# brushless_sub_driver_4.net
KiCad netlist of a schematic drawn in EAGLE
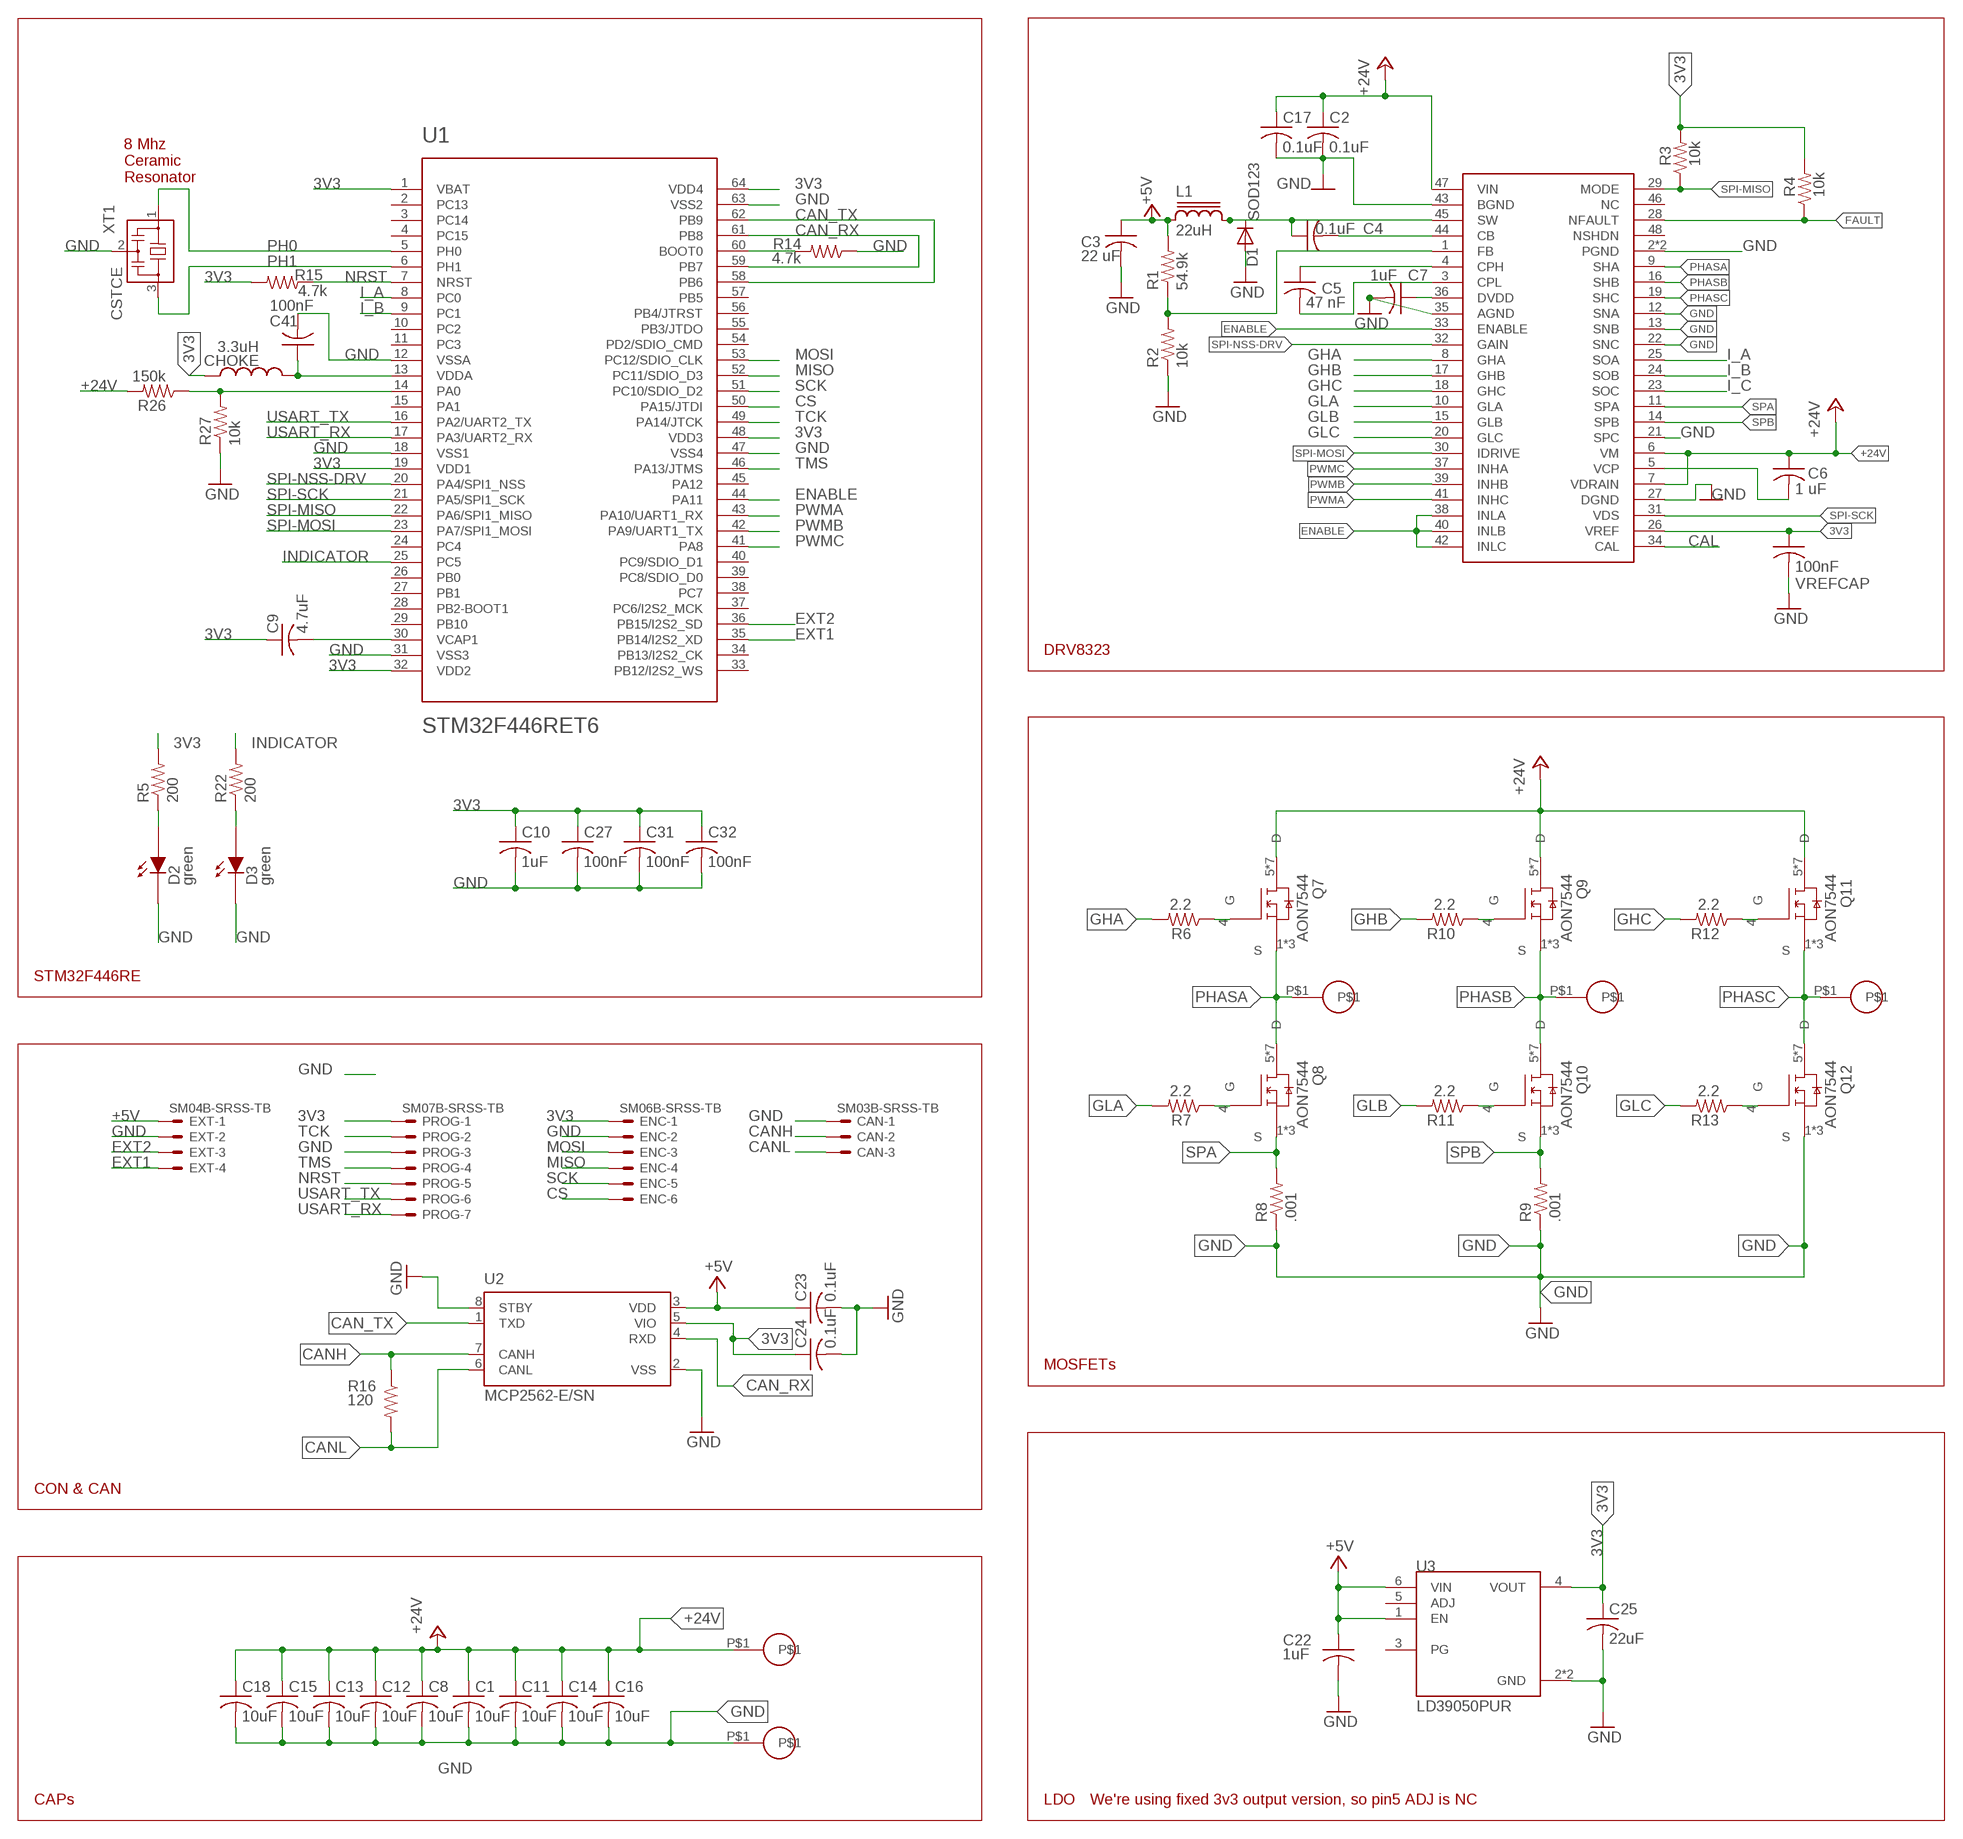
[diagram p0: schematic, sheet 1]

(export (version "E")
  (design (tool "Eeschema 10.0.6"))
  (components
    (comp (ref "C1")
      (value "10uF")
      (footprint "eagle-import:C1206K")
      (libsource (lib "eagle-import") (part "C-USC1206K"))
    )
    (comp (ref "C2")
      (value "0.1uF")
      (footprint "eagle-import:C0603K")
      (libsource (lib "eagle-import") (part "C-USC0603K"))
    )
    (comp (ref "C3")
      (value "22 uF")
      (footprint "eagle-import:C0603K")
      (libsource (lib "eagle-import") (part "C-USC0603K"))
    )
    (comp (ref "C4")
      (value "0.1uF")
      (footprint "eagle-import:C0603K")
      (libsource (lib "eagle-import") (part "C-USC0603K"))
    )
    (comp (ref "C5")
      (value "47 nF")
      (footprint "eagle-import:C0402K")
      (libsource (lib "eagle-import") (part "C-USC0402K"))
    )
    (comp (ref "C6")
      (value "1 uF")
      (footprint "eagle-import:C0603K")
      (libsource (lib "eagle-import") (part "C-USC0603K"))
    )
    (comp (ref "C7")
      (value "1uF")
      (footprint "eagle-import:C0402K")
      (libsource (lib "eagle-import") (part "C-USC0402K"))
    )
    (comp (ref "C8")
      (value "10uF")
      (footprint "eagle-import:C1206K")
      (libsource (lib "eagle-import") (part "C-USC1206K"))
    )
    (comp (ref "C9")
      (value "4.7uF")
      (footprint "eagle-import:C0402K")
      (libsource (lib "eagle-import") (part "C-USC0402K"))
    )
    (comp (ref "C10")
      (value "1uF")
      (footprint "eagle-import:C0402K")
      (libsource (lib "eagle-import") (part "C-USC0402K"))
    )
    (comp (ref "C11")
      (value "10uF")
      (footprint "eagle-import:C1206K")
      (libsource (lib "eagle-import") (part "C-USC1206K"))
    )
    (comp (ref "C12")
      (value "10uF")
      (footprint "eagle-import:C1206K")
      (libsource (lib "eagle-import") (part "C-USC1206K"))
    )
    (comp (ref "C13")
      (value "10uF")
      (footprint "eagle-import:C1206K")
      (libsource (lib "eagle-import") (part "C-USC1206K"))
    )
    (comp (ref "C14")
      (value "10uF")
      (footprint "eagle-import:C1206K")
      (libsource (lib "eagle-import") (part "C-USC1206K"))
    )
    (comp (ref "C15")
      (value "10uF")
      (footprint "eagle-import:C1206K")
      (libsource (lib "eagle-import") (part "C-USC1206K"))
    )
    (comp (ref "C16")
      (value "10uF")
      (footprint "eagle-import:C1206K")
      (libsource (lib "eagle-import") (part "C-USC1206K"))
    )
    (comp (ref "C17")
      (value "0.1uF")
      (footprint "eagle-import:C1206K")
      (libsource (lib "eagle-import") (part "C-USC1206K"))
    )
    (comp (ref "C18")
      (value "10uF")
      (footprint "eagle-import:C1206K")
      (libsource (lib "eagle-import") (part "C-USC1206K"))
    )
    (comp (ref "C22")
      (value "1uF")
      (footprint "eagle-import:C0402")
      (libsource (lib "eagle-import") (part "C-USC0402"))
    )
    (comp (ref "C23")
      (value "0.1uF")
      (footprint "eagle-import:C0603K")
      (libsource (lib "eagle-import") (part "C-USC0603K"))
    )
    (comp (ref "C24")
      (value "0.1uF")
      (footprint "eagle-import:C0603K")
      (libsource (lib "eagle-import") (part "C-USC0603K"))
    )
    (comp (ref "C25")
      (value "22uF")
      (footprint "eagle-import:C0603K")
      (libsource (lib "eagle-import") (part "C-USC0603K"))
    )
    (comp (ref "C27")
      (value "100nF")
      (footprint "eagle-import:C0402K")
      (libsource (lib "eagle-import") (part "C-USC0402K"))
    )
    (comp (ref "C31")
      (value "100nF")
      (footprint "eagle-import:C0402K")
      (libsource (lib "eagle-import") (part "C-USC0402K"))
    )
    (comp (ref "C32")
      (value "100nF")
      (footprint "eagle-import:C0402K")
      (libsource (lib "eagle-import") (part "C-USC0402K"))
    )
    (comp (ref "C41")
      (value "100nF")
      (footprint "eagle-import:C0402")
      (libsource (lib "eagle-import") (part "C-USC0402"))
    )
    (comp (ref "CAN")
      (value "SM03B-SRSS-TB")
      (footprint "eagle-import:SM03B-SRSS-TB")
      (libsource (lib "eagle-import") (part "?M03B-SRSS-TBS"))
    )
    (comp (ref "CHOKE")
      (value "3.3uH")
      (footprint "eagle-import:0603")
      (libsource (lib "eagle-import") (part "INDUCTOR0603"))
    )
    (comp (ref "D1")
      (value "SOD123")
      (footprint "eagle-import:SOD123")
      (libsource (lib "eagle-import") (part "DIODE-SOD123"))
    )
    (comp (ref "D2")
      (value "green")
      (footprint "eagle-import:0603P")
      (libsource (lib "eagle-import") (part "LEDB"))
    )
    (comp (ref "D3")
      (value "green")
      (footprint "eagle-import:0603P")
      (libsource (lib "eagle-import") (part "LEDB"))
    )
    (comp (ref "DRV1")
      (value "DRV8323RH")
      (footprint "eagle-import:QFN50P700X700X90-49N")
      (libsource (lib "eagle-import") (part "DRV8323RH"))
    )
    (comp (ref "ENC")
      (value "SM06B-SRSS-TB")
      (footprint "eagle-import:SM06B-SRSS-TB")
      (libsource (lib "eagle-import") (part "?M06B-SRSS-TBS"))
    )
    (comp (ref "EXT")
      (value "SM04B-SRSS-TB")
      (footprint "eagle-import:SM04B-SRSS-TB")
      (libsource (lib "eagle-import") (part "?M04B-SRSS-TBS"))
    )
    (comp (ref "L1")
      (value "22uH")
      (footprint "eagle-import:SDR0302")
      (libsource (lib "eagle-import") (part "SDR0302"))
    )
    (comp (ref "O_A")
      (value "18_AWG_PAD")
      (footprint "eagle-import:18_AWG_PAD")
      (libsource (lib "eagle-import") (part "18_AWG_PAD"))
    )
    (comp (ref "O_B")
      (value "18_AWG_PAD")
      (footprint "eagle-import:18_AWG_PAD")
      (libsource (lib "eagle-import") (part "18_AWG_PAD"))
    )
    (comp (ref "O_C")
      (value "18_AWG_PAD")
      (footprint "eagle-import:18_AWG_PAD")
      (libsource (lib "eagle-import") (part "18_AWG_PAD"))
    )
    (comp (ref "PROG")
      (value "SM07B-SRSS-TB")
      (footprint "eagle-import:SM07B-SRSS-TB")
      (libsource (lib "eagle-import") (part "?M07B-SRSS-TBS"))
    )
    (comp (ref "Q7")
      (value "AON7544")
      (footprint "eagle-import:AON7544")
      (libsource (lib "eagle-import") (part "AON7544"))
    )
    (comp (ref "Q8")
      (value "AON7544")
      (footprint "eagle-import:AON7544")
      (libsource (lib "eagle-import") (part "AON7544"))
    )
    (comp (ref "Q9")
      (value "AON7544")
      (footprint "eagle-import:AON7544")
      (libsource (lib "eagle-import") (part "AON7544"))
    )
    (comp (ref "Q10")
      (value "AON7544")
      (footprint "eagle-import:AON7544")
      (libsource (lib "eagle-import") (part "AON7544"))
    )
    (comp (ref "Q11")
      (value "AON7544")
      (footprint "eagle-import:AON7544")
      (libsource (lib "eagle-import") (part "AON7544"))
    )
    (comp (ref "Q12")
      (value "AON7544")
      (footprint "eagle-import:AON7544")
      (libsource (lib "eagle-import") (part "AON7544"))
    )
    (comp (ref "R1")
      (value "54.9k")
      (footprint "eagle-import:R0402")
      (libsource (lib "eagle-import") (part "R-US_R0402"))
    )
    (comp (ref "R2")
      (value "10k")
      (footprint "eagle-import:R0402")
      (libsource (lib "eagle-import") (part "R-US_R0402"))
    )
    (comp (ref "R3")
      (value "10k")
      (footprint "eagle-import:R0402")
      (libsource (lib "eagle-import") (part "R-US_R0402"))
    )
    (comp (ref "R4")
      (value "10k")
      (footprint "eagle-import:R0402")
      (libsource (lib "eagle-import") (part "R-US_R0402"))
    )
    (comp (ref "R5")
      (value "200")
      (footprint "eagle-import:R0402")
      (libsource (lib "eagle-import") (part "R-US_R0402"))
    )
    (comp (ref "R6")
      (value "2.2")
      (footprint "eagle-import:R0402")
      (libsource (lib "eagle-import") (part "R-US_R0402"))
    )
    (comp (ref "R7")
      (value "2.2")
      (footprint "eagle-import:R0402")
      (libsource (lib "eagle-import") (part "R-US_R0402"))
    )
    (comp (ref "R8")
      (value ".001")
      (footprint "eagle-import:R1210")
      (libsource (lib "eagle-import") (part "R-US_R1210"))
    )
    (comp (ref "R9")
      (value ".001")
      (footprint "eagle-import:R1210")
      (libsource (lib "eagle-import") (part "R-US_R1210"))
    )
    (comp (ref "R10")
      (value "2.2")
      (footprint "eagle-import:R0402")
      (libsource (lib "eagle-import") (part "R-US_R0402"))
    )
    (comp (ref "R11")
      (value "2.2")
      (footprint "eagle-import:R0402")
      (libsource (lib "eagle-import") (part "R-US_R0402"))
    )
    (comp (ref "R12")
      (value "2.2")
      (footprint "eagle-import:R0402")
      (libsource (lib "eagle-import") (part "R-US_R0402"))
    )
    (comp (ref "R13")
      (value "2.2")
      (footprint "eagle-import:R0402")
      (libsource (lib "eagle-import") (part "R-US_R0402"))
    )
    (comp (ref "R14")
      (value "4.7k")
      (footprint "eagle-import:R0402")
      (libsource (lib "eagle-import") (part "R-US_R0402"))
    )
    (comp (ref "R15")
      (value "4.7k")
      (footprint "eagle-import:R0402")
      (libsource (lib "eagle-import") (part "R-US_R0402"))
    )
    (comp (ref "R16")
      (value "120")
      (footprint "eagle-import:R0603")
      (libsource (lib "eagle-import") (part "R-US_R0603"))
    )
    (comp (ref "R22")
      (value "200")
      (footprint "eagle-import:R0402")
      (libsource (lib "eagle-import") (part "R-US_R0402"))
    )
    (comp (ref "R26")
      (value "150k")
      (footprint "eagle-import:R0402")
      (libsource (lib "eagle-import") (part "R-US_R0402"))
    )
    (comp (ref "R27")
      (value "10k")
      (footprint "eagle-import:R0402")
      (libsource (lib "eagle-import") (part "R-US_R0402"))
    )
    (comp (ref "U$8")
      (value "18_AWG_PAD")
      (footprint "eagle-import:18_AWG_PAD")
      (libsource (lib "eagle-import") (part "18_AWG_PAD"))
    )
    (comp (ref "U$10")
      (value "18_AWG_PAD")
      (footprint "eagle-import:18_AWG_PAD")
      (libsource (lib "eagle-import") (part "18_AWG_PAD"))
    )
    (comp (ref "U1")
      (value "STM32F446RET6")
      (footprint "eagle-import:TQFP64")
      (libsource (lib "eagle-import") (part "STM32F446RET6"))
    )
    (comp (ref "U2")
      (value "MCP2562-E/SN")
      (footprint "eagle-import:SOIC127P600X175-8N")
      (fields (field (name "MF") "Microchip"))
      (libsource (lib "eagle-import") (part "MCP2562-E/SN"))
    )
    (comp (ref "U3")
      (value "LD39050PUR")
      (footprint "eagle-import:SON95P300X300X100-7N")
      (fields (field (name "MF") "STMicroelectronics"))
      (libsource (lib "eagle-import") (part "LD39050PUR"))
    )
    (comp (ref "VREFCAP")
      (value "100nF")
      (footprint "eagle-import:C0402K")
      (libsource (lib "eagle-import") (part "C-USC0402K"))
    )
    (comp (ref "XT1")
      (value "CSTCE")
      (footprint "eagle-import:CSTCE")
      (libsource (lib "eagle-import") (part "CSTCE"))
    )
  )
  (nets
    (net (code "1") (name "+5V") (class "Default")
      (node (ref "C22") (pin "1") (pinfunction "1_1") (pintype "passive"))
      (node (ref "C23") (pin "1") (pinfunction "1_1") (pintype "passive"))
      (node (ref "C3") (pin "1") (pinfunction "1_1") (pintype "passive"))
      (node (ref "EXT") (pin "1") (pinfunction "S_1") (pintype "passive"))
      (node (ref "L1") (pin "1") (pinfunction "1_1") (pintype "passive"))
      (node (ref "R1") (pin "2") (pinfunction "2_2") (pintype "passive"))
      (node (ref "U2") (pin "3") (pinfunction "VDD_3") (pintype "power_in"))
      (node (ref "U3") (pin "1") (pinfunction "EN_1") (pintype "input"))
      (node (ref "U3") (pin "6") (pinfunction "VIN_6") (pintype "input"))
    )
    (net (code "2") (name "+24V") (class "Default")
      (node (ref "C1") (pin "1") (pinfunction "1_1") (pintype "passive"))
      (node (ref "C11") (pin "1") (pinfunction "1_1") (pintype "passive"))
      (node (ref "C12") (pin "1") (pinfunction "1_1") (pintype "passive"))
      (node (ref "C13") (pin "1") (pinfunction "1_1") (pintype "passive"))
      (node (ref "C14") (pin "1") (pinfunction "1_1") (pintype "passive"))
      (node (ref "C15") (pin "1") (pinfunction "1_1") (pintype "passive"))
      (node (ref "C16") (pin "1") (pinfunction "1_1") (pintype "passive"))
      (node (ref "C17") (pin "1") (pinfunction "1_1") (pintype "passive"))
      (node (ref "C18") (pin "1") (pinfunction "1_1") (pintype "passive"))
      (node (ref "C2") (pin "1") (pinfunction "1_1") (pintype "passive"))
      (node (ref "C6") (pin "1") (pinfunction "1_1") (pintype "passive"))
      (node (ref "C8") (pin "1") (pinfunction "1_1") (pintype "passive"))
      (node (ref "DRV1") (pin "47") (pinfunction "VIN_47") (pintype "bidirectional"))
      (node (ref "DRV1") (pin "6") (pinfunction "VM_6") (pintype "bidirectional"))
      (node (ref "DRV1") (pin "7") (pinfunction "VDRAIN_7") (pintype "bidirectional"))
      (node (ref "Q11") (pin "10") (pinfunction "D_10") (pintype "bidirectional"))
      (node (ref "Q11") (pin "11") (pinfunction "D_11") (pintype "bidirectional"))
      (node (ref "Q11") (pin "5") (pinfunction "D_5") (pintype "bidirectional"))
      (node (ref "Q11") (pin "6") (pinfunction "D_6") (pintype "bidirectional"))
      (node (ref "Q11") (pin "7") (pinfunction "D_7") (pintype "bidirectional"))
      (node (ref "Q11") (pin "8") (pinfunction "D_8") (pintype "bidirectional"))
      (node (ref "Q11") (pin "9") (pinfunction "D_9") (pintype "bidirectional"))
      (node (ref "Q7") (pin "10") (pinfunction "D_10") (pintype "bidirectional"))
      (node (ref "Q7") (pin "11") (pinfunction "D_11") (pintype "bidirectional"))
      (node (ref "Q7") (pin "5") (pinfunction "D_5") (pintype "bidirectional"))
      (node (ref "Q7") (pin "6") (pinfunction "D_6") (pintype "bidirectional"))
      (node (ref "Q7") (pin "7") (pinfunction "D_7") (pintype "bidirectional"))
      (node (ref "Q7") (pin "8") (pinfunction "D_8") (pintype "bidirectional"))
      (node (ref "Q7") (pin "9") (pinfunction "D_9") (pintype "bidirectional"))
      (node (ref "Q9") (pin "10") (pinfunction "D_10") (pintype "bidirectional"))
      (node (ref "Q9") (pin "11") (pinfunction "D_11") (pintype "bidirectional"))
      (node (ref "Q9") (pin "5") (pinfunction "D_5") (pintype "bidirectional"))
      (node (ref "Q9") (pin "6") (pinfunction "D_6") (pintype "bidirectional"))
      (node (ref "Q9") (pin "7") (pinfunction "D_7") (pintype "bidirectional"))
      (node (ref "Q9") (pin "8") (pinfunction "D_8") (pintype "bidirectional"))
      (node (ref "Q9") (pin "9") (pinfunction "D_9") (pintype "bidirectional"))
      (node (ref "R26") (pin "2") (pinfunction "2_2") (pintype "passive"))
      (node (ref "U$8") (pin "P$1") (pinfunction "P$1_P$1") (pintype "bidirectional"))
    )
    (net (code "3") (name "/CAL") (class "Default")
      (node (ref "DRV1") (pin "34") (pinfunction "CAL_34") (pintype "bidirectional"))
    )
    (net (code "4") (name "/CS") (class "Default")
      (node (ref "ENC") (pin "6") (pinfunction "S_6") (pintype "passive"))
      (node (ref "U1") (pin "50") (pinfunction "PA15/JTDI_50") (pintype "bidirectional"))
    )
    (net (code "5") (name "/EXT1") (class "Default")
      (node (ref "EXT") (pin "4") (pinfunction "S_4") (pintype "passive"))
      (node (ref "U1") (pin "35") (pinfunction "PB14/I2S2_XD_35") (pintype "bidirectional"))
    )
    (net (code "6") (name "/EXT2") (class "Default")
      (node (ref "EXT") (pin "3") (pinfunction "S_3") (pintype "passive"))
      (node (ref "U1") (pin "36") (pinfunction "PB15/I2S2_SD_36") (pintype "bidirectional"))
    )
    (net (code "7") (name "/INDICATOR") (class "Default")
      (node (ref "R22") (pin "2") (pinfunction "2_2") (pintype "passive"))
      (node (ref "U1") (pin "25") (pinfunction "PC5_25") (pintype "bidirectional"))
    )
    (net (code "8") (name "/I_A") (class "Default")
      (node (ref "DRV1") (pin "25") (pinfunction "SOA_25") (pintype "bidirectional"))
      (node (ref "U1") (pin "8") (pinfunction "PC0_8") (pintype "bidirectional"))
    )
    (net (code "9") (name "/I_B") (class "Default")
      (node (ref "DRV1") (pin "24") (pinfunction "SOB_24") (pintype "bidirectional"))
      (node (ref "U1") (pin "9") (pinfunction "PC1_9") (pintype "bidirectional"))
    )
    (net (code "10") (name "/I_C") (class "Default")
      (node (ref "DRV1") (pin "23") (pinfunction "SOC_23") (pintype "bidirectional"))
    )
    (net (code "11") (name "/MISO") (class "Default")
      (node (ref "ENC") (pin "4") (pinfunction "S_4") (pintype "passive"))
      (node (ref "U1") (pin "52") (pinfunction "PC11/SDIO_D3_52") (pintype "bidirectional"))
    )
    (net (code "12") (name "/MOSI") (class "Default")
      (node (ref "ENC") (pin "3") (pinfunction "S_3") (pintype "passive"))
      (node (ref "U1") (pin "53") (pinfunction "PC12/SDIO_CLK_53") (pintype "bidirectional"))
    )
    (net (code "13") (name "/NRST") (class "Default")
      (node (ref "PROG") (pin "5") (pinfunction "S_5") (pintype "passive"))
      (node (ref "R15") (pin "1") (pinfunction "1_1") (pintype "passive"))
      (node (ref "U1") (pin "7") (pinfunction "NRST_7") (pintype "bidirectional"))
    )
    (net (code "14") (name "/PH0") (class "Default")
      (node (ref "U1") (pin "5") (pinfunction "PH0_5") (pintype "bidirectional"))
      (node (ref "XT1") (pin "1") (pinfunction "1_1") (pintype "passive"))
    )
    (net (code "15") (name "/PH1") (class "Default")
      (node (ref "U1") (pin "6") (pinfunction "PH1_6") (pintype "bidirectional"))
      (node (ref "XT1") (pin "3") (pinfunction "3_3") (pintype "passive"))
    )
    (net (code "16") (name "/SCK") (class "Default")
      (node (ref "ENC") (pin "5") (pinfunction "S_5") (pintype "passive"))
      (node (ref "U1") (pin "51") (pinfunction "PC10/SDIO_D2_51") (pintype "bidirectional"))
    )
    (net (code "17") (name "/TCK") (class "Default")
      (node (ref "PROG") (pin "2") (pinfunction "S_2") (pintype "passive"))
      (node (ref "U1") (pin "49") (pinfunction "PA14/JTCK_49") (pintype "bidirectional"))
    )
    (net (code "18") (name "/TMS") (class "Default")
      (node (ref "PROG") (pin "4") (pinfunction "S_4") (pintype "passive"))
      (node (ref "U1") (pin "46") (pinfunction "PA13/JTMS_46") (pintype "bidirectional"))
    )
    (net (code "19") (name "/USART_RX") (class "Default")
      (node (ref "PROG") (pin "7") (pinfunction "S_7") (pintype "passive"))
      (node (ref "U1") (pin "17") (pinfunction "PA3/UART2_RX_17") (pintype "bidirectional"))
    )
    (net (code "20") (name "/USART_TX") (class "Default")
      (node (ref "PROG") (pin "6") (pinfunction "S_6") (pintype "passive"))
      (node (ref "U1") (pin "16") (pinfunction "PA2/UART2_TX_16") (pintype "bidirectional"))
    )
    (net (code "21") (name "3V3") (class "Default")
      (node (ref "C10") (pin "1") (pinfunction "1_1") (pintype "passive"))
      (node (ref "C24") (pin "1") (pinfunction "1_1") (pintype "passive"))
      (node (ref "C25") (pin "1") (pinfunction "1_1") (pintype "passive"))
      (node (ref "C27") (pin "1") (pinfunction "1_1") (pintype "passive"))
      (node (ref "C31") (pin "1") (pinfunction "1_1") (pintype "passive"))
      (node (ref "C32") (pin "1") (pinfunction "1_1") (pintype "passive"))
      (node (ref "C9") (pin "1") (pinfunction "1_1") (pintype "passive"))
      (node (ref "CHOKE") (pin "1") (pinfunction "1_1") (pintype "passive"))
      (node (ref "DRV1") (pin "26") (pinfunction "VREF_26") (pintype "bidirectional"))
      (node (ref "ENC") (pin "1") (pinfunction "S_1") (pintype "passive"))
      (node (ref "PROG") (pin "1") (pinfunction "S_1") (pintype "passive"))
      (node (ref "R15") (pin "2") (pinfunction "2_2") (pintype "passive"))
      (node (ref "R3") (pin "2") (pinfunction "2_2") (pintype "passive"))
      (node (ref "R4") (pin "2") (pinfunction "2_2") (pintype "passive"))
      (node (ref "R5") (pin "2") (pinfunction "2_2") (pintype "passive"))
      (node (ref "U1") (pin "1") (pinfunction "VBAT_1") (pintype "bidirectional"))
      (node (ref "U1") (pin "19") (pinfunction "VDD1_19") (pintype "bidirectional"))
      (node (ref "U1") (pin "32") (pinfunction "VDD2_32") (pintype "bidirectional"))
      (node (ref "U1") (pin "48") (pinfunction "VDD3_48") (pintype "bidirectional"))
      (node (ref "U1") (pin "64") (pinfunction "VDD4_64") (pintype "bidirectional"))
      (node (ref "U2") (pin "5") (pinfunction "VIO_5") (pintype "power_in"))
      (node (ref "U3") (pin "4") (pinfunction "VOUT_4") (pintype "output"))
      (node (ref "VREFCAP") (pin "1") (pinfunction "1_1") (pintype "passive"))
    )
    (net (code "22") (name "CANH") (class "Default")
      (node (ref "CAN") (pin "2") (pinfunction "S_2") (pintype "passive"))
      (node (ref "R16") (pin "1") (pinfunction "1_1") (pintype "passive"))
      (node (ref "U2") (pin "7") (pinfunction "CANH_7") (pintype "input"))
    )
    (net (code "23") (name "CANL") (class "Default")
      (node (ref "CAN") (pin "3") (pinfunction "S_3") (pintype "passive"))
      (node (ref "R16") (pin "2") (pinfunction "2_2") (pintype "passive"))
      (node (ref "U2") (pin "6") (pinfunction "CANL_6") (pintype "input"))
    )
    (net (code "24") (name "CAN_RX") (class "Default")
      (node (ref "U1") (pin "59") (pinfunction "PB7_59") (pintype "bidirectional"))
      (node (ref "U1") (pin "61") (pinfunction "PB8_61") (pintype "bidirectional"))
      (node (ref "U2") (pin "4") (pinfunction "RXD_4") (pintype "output"))
    )
    (net (code "25") (name "CAN_TX") (class "Default")
      (node (ref "U1") (pin "58") (pinfunction "PB6_58") (pintype "bidirectional"))
      (node (ref "U1") (pin "62") (pinfunction "PB9_62") (pintype "bidirectional"))
      (node (ref "U2") (pin "1") (pinfunction "TXD_1") (pintype "input"))
    )
    (net (code "26") (name "ENABLE") (class "Default")
      (node (ref "DRV1") (pin "33") (pinfunction "ENABLE_33") (pintype "bidirectional"))
      (node (ref "DRV1") (pin "38") (pinfunction "INLA_38") (pintype "bidirectional"))
      (node (ref "DRV1") (pin "40") (pinfunction "INLB_40") (pintype "bidirectional"))
      (node (ref "DRV1") (pin "42") (pinfunction "INLC_42") (pintype "bidirectional"))
      (node (ref "U1") (pin "44") (pinfunction "PA11_44") (pintype "bidirectional"))
    )
    (net (code "27") (name "FAULT") (class "Default")
      (node (ref "DRV1") (pin "28") (pinfunction "NFAULT_28") (pintype "bidirectional"))
      (node (ref "R4") (pin "1") (pinfunction "1_1") (pintype "passive"))
    )
    (net (code "28") (name "GHA") (class "Default")
      (node (ref "DRV1") (pin "8") (pinfunction "GHA_8") (pintype "bidirectional"))
      (node (ref "R6") (pin "2") (pinfunction "2_2") (pintype "passive"))
    )
    (net (code "29") (name "GHB") (class "Default")
      (node (ref "DRV1") (pin "17") (pinfunction "GHB_17") (pintype "bidirectional"))
      (node (ref "R10") (pin "2") (pinfunction "2_2") (pintype "passive"))
    )
    (net (code "30") (name "GHC") (class "Default")
      (node (ref "DRV1") (pin "18") (pinfunction "GHC_18") (pintype "bidirectional"))
      (node (ref "R12") (pin "2") (pinfunction "2_2") (pintype "passive"))
    )
    (net (code "31") (name "GLA") (class "Default")
      (node (ref "DRV1") (pin "10") (pinfunction "GLA_10") (pintype "bidirectional"))
      (node (ref "R7") (pin "2") (pinfunction "2_2") (pintype "passive"))
    )
    (net (code "32") (name "GLB") (class "Default")
      (node (ref "DRV1") (pin "15") (pinfunction "GLB_15") (pintype "bidirectional"))
      (node (ref "R11") (pin "2") (pinfunction "2_2") (pintype "passive"))
    )
    (net (code "33") (name "GLC") (class "Default")
      (node (ref "DRV1") (pin "20") (pinfunction "GLC_20") (pintype "bidirectional"))
      (node (ref "R13") (pin "2") (pinfunction "2_2") (pintype "passive"))
    )
    (net (code "34") (name "GND") (class "Default")
      (node (ref "C1") (pin "2") (pinfunction "2_2") (pintype "passive"))
      (node (ref "C10") (pin "2") (pinfunction "2_2") (pintype "passive"))
      (node (ref "C11") (pin "2") (pinfunction "2_2") (pintype "passive"))
      (node (ref "C12") (pin "2") (pinfunction "2_2") (pintype "passive"))
      (node (ref "C13") (pin "2") (pinfunction "2_2") (pintype "passive"))
      (node (ref "C14") (pin "2") (pinfunction "2_2") (pintype "passive"))
      (node (ref "C15") (pin "2") (pinfunction "2_2") (pintype "passive"))
      (node (ref "C16") (pin "2") (pinfunction "2_2") (pintype "passive"))
      (node (ref "C17") (pin "2") (pinfunction "2_2") (pintype "passive"))
      (node (ref "C18") (pin "2") (pinfunction "2_2") (pintype "passive"))
      (node (ref "C2") (pin "2") (pinfunction "2_2") (pintype "passive"))
      (node (ref "C22") (pin "2") (pinfunction "2_2") (pintype "passive"))
      (node (ref "C23") (pin "2") (pinfunction "2_2") (pintype "passive"))
      (node (ref "C24") (pin "2") (pinfunction "2_2") (pintype "passive"))
      (node (ref "C25") (pin "2") (pinfunction "2_2") (pintype "passive"))
      (node (ref "C27") (pin "2") (pinfunction "2_2") (pintype "passive"))
      (node (ref "C3") (pin "2") (pinfunction "2_2") (pintype "passive"))
      (node (ref "C31") (pin "2") (pinfunction "2_2") (pintype "passive"))
      (node (ref "C32") (pin "2") (pinfunction "2_2") (pintype "passive"))
      (node (ref "C41") (pin "2") (pinfunction "2_2") (pintype "passive"))
      (node (ref "C7") (pin "2") (pinfunction "2_2") (pintype "passive"))
      (node (ref "C8") (pin "2") (pinfunction "2_2") (pintype "passive"))
      (node (ref "CAN") (pin "1") (pinfunction "S_1") (pintype "passive"))
      (node (ref "D1") (pin "A") (pinfunction "A_A") (pintype "passive"))
      (node (ref "D2") (pin "2") (pinfunction "D_OUT_2") (pintype "passive"))
      (node (ref "D3") (pin "2") (pinfunction "D_OUT_2") (pintype "passive"))
      (node (ref "DRV1") (pin "12") (pinfunction "SNA_12") (pintype "bidirectional"))
      (node (ref "DRV1") (pin "13") (pinfunction "SNB_13") (pintype "bidirectional"))
      (node (ref "DRV1") (pin "2") (pinfunction "PGND_2") (pintype "bidirectional"))
      (node (ref "DRV1") (pin "21") (pinfunction "SPC_21") (pintype "bidirectional"))
      (node (ref "DRV1") (pin "22") (pinfunction "SNC_22") (pintype "bidirectional"))
      (node (ref "DRV1") (pin "27") (pinfunction "DGND_27") (pintype "bidirectional"))
      (node (ref "DRV1") (pin "35") (pinfunction "AGND_35") (pintype "bidirectional"))
      (node (ref "DRV1") (pin "43") (pinfunction "BGND_43") (pintype "bidirectional"))
      (node (ref "DRV1") (pin "49") (pinfunction "PGND_49") (pintype "bidirectional"))
      (node (ref "ENC") (pin "2") (pinfunction "S_2") (pintype "passive"))
      (node (ref "EXT") (pin "2") (pinfunction "S_2") (pintype "passive"))
      (node (ref "PROG") (pin "3") (pinfunction "S_3") (pintype "passive"))
      (node (ref "Q12") (pin "1") (pinfunction "S_1") (pintype "bidirectional"))
      (node (ref "Q12") (pin "2") (pinfunction "S_2") (pintype "bidirectional"))
      (node (ref "Q12") (pin "3") (pinfunction "S_3") (pintype "bidirectional"))
      (node (ref "R14") (pin "1") (pinfunction "1_1") (pintype "passive"))
      (node (ref "R2") (pin "1") (pinfunction "1_1") (pintype "passive"))
      (node (ref "R27") (pin "1") (pinfunction "1_1") (pintype "passive"))
      (node (ref "R8") (pin "1") (pinfunction "1_1") (pintype "passive"))
      (node (ref "R9") (pin "1") (pinfunction "1_1") (pintype "passive"))
      (node (ref "U$10") (pin "P$1") (pinfunction "P$1_P$1") (pintype "bidirectional"))
      (node (ref "U1") (pin "12") (pinfunction "VSSA_12") (pintype "bidirectional"))
      (node (ref "U1") (pin "18") (pinfunction "VSS1_18") (pintype "bidirectional"))
      (node (ref "U1") (pin "31") (pinfunction "VSS3_31") (pintype "bidirectional"))
      (node (ref "U1") (pin "47") (pinfunction "VSS4_47") (pintype "bidirectional"))
      (node (ref "U1") (pin "63") (pinfunction "VSS2_63") (pintype "bidirectional"))
      (node (ref "U2") (pin "2") (pinfunction "VSS_2") (pintype "power_in"))
      (node (ref "U2") (pin "8") (pinfunction "STBY_8") (pintype "input"))
      (node (ref "U3") (pin "2") (pinfunction "GND_2") (pintype "power_in"))
      (node (ref "U3") (pin "7") (pinfunction "GND_7") (pintype "power_in"))
      (node (ref "VREFCAP") (pin "2") (pinfunction "2_2") (pintype "passive"))
      (node (ref "XT1") (pin "2") (pinfunction "2_2") (pintype "passive"))
    )
    (net (code "35") (name "Net-(D2-D_IN)") (class "Default")
      (node (ref "D2") (pin "1") (pinfunction "D_IN_1") (pintype "passive"))
      (node (ref "R5") (pin "1") (pinfunction "1_1") (pintype "passive"))
    )
    (net (code "36") (name "Net-(D3-D_IN)") (class "Default")
      (node (ref "D3") (pin "1") (pinfunction "D_IN_1") (pintype "passive"))
      (node (ref "R22") (pin "1") (pinfunction "1_1") (pintype "passive"))
    )
    (net (code "37") (name "Net-(DRV1-CB)") (class "Default")
      (node (ref "C4") (pin "2") (pinfunction "2_2") (pintype "passive"))
      (node (ref "DRV1") (pin "44") (pinfunction "CB_44") (pintype "bidirectional"))
    )
    (net (code "38") (name "Net-(DRV1-CPH)") (class "Default")
      (node (ref "C5") (pin "1") (pinfunction "1_1") (pintype "passive"))
      (node (ref "DRV1") (pin "4") (pinfunction "CPH_4") (pintype "bidirectional"))
    )
    (net (code "39") (name "Net-(DRV1-CPL)") (class "Default")
      (node (ref "C5") (pin "2") (pinfunction "2_2") (pintype "passive"))
      (node (ref "DRV1") (pin "3") (pinfunction "CPL_3") (pintype "bidirectional"))
    )
    (net (code "40") (name "Net-(DRV1-DVDD)") (class "Default")
      (node (ref "C7") (pin "1") (pinfunction "1_1") (pintype "passive"))
      (node (ref "DRV1") (pin "36") (pinfunction "DVDD_36") (pintype "bidirectional"))
    )
    (net (code "41") (name "Net-(DRV1-FB)") (class "Default")
      (node (ref "DRV1") (pin "1") (pinfunction "FB_1") (pintype "bidirectional"))
      (node (ref "R1") (pin "1") (pinfunction "1_1") (pintype "passive"))
      (node (ref "R2") (pin "2") (pinfunction "2_2") (pintype "passive"))
    )
    (net (code "42") (name "Net-(DRV1-SW)") (class "Default")
      (node (ref "C4") (pin "1") (pinfunction "1_1") (pintype "passive"))
      (node (ref "D1") (pin "C") (pinfunction "C_C") (pintype "passive"))
      (node (ref "DRV1") (pin "45") (pinfunction "SW_45") (pintype "bidirectional"))
      (node (ref "L1") (pin "2") (pinfunction "2_2") (pintype "passive"))
    )
    (net (code "43") (name "Net-(DRV1-VCP)") (class "Default")
      (node (ref "C6") (pin "2") (pinfunction "2_2") (pintype "passive"))
      (node (ref "DRV1") (pin "5") (pinfunction "VCP_5") (pintype "bidirectional"))
    )
    (net (code "44") (name "Net-(Q7-G)") (class "Default")
      (node (ref "Q7") (pin "4") (pinfunction "G_4") (pintype "bidirectional"))
      (node (ref "R6") (pin "1") (pinfunction "1_1") (pintype "passive"))
    )
    (net (code "45") (name "Net-(Q8-G)") (class "Default")
      (node (ref "Q8") (pin "4") (pinfunction "G_4") (pintype "bidirectional"))
      (node (ref "R7") (pin "1") (pinfunction "1_1") (pintype "passive"))
    )
    (net (code "46") (name "Net-(Q9-G)") (class "Default")
      (node (ref "Q9") (pin "4") (pinfunction "G_4") (pintype "bidirectional"))
      (node (ref "R10") (pin "1") (pinfunction "1_1") (pintype "passive"))
    )
    (net (code "47") (name "Net-(Q10-G)") (class "Default")
      (node (ref "Q10") (pin "4") (pinfunction "G_4") (pintype "bidirectional"))
      (node (ref "R11") (pin "1") (pinfunction "1_1") (pintype "passive"))
    )
    (net (code "48") (name "Net-(Q11-G)") (class "Default")
      (node (ref "Q11") (pin "4") (pinfunction "G_4") (pintype "bidirectional"))
      (node (ref "R12") (pin "1") (pinfunction "1_1") (pintype "passive"))
    )
    (net (code "49") (name "Net-(Q12-G)") (class "Default")
      (node (ref "Q12") (pin "4") (pinfunction "G_4") (pintype "bidirectional"))
      (node (ref "R13") (pin "1") (pinfunction "1_1") (pintype "passive"))
    )
    (net (code "50") (name "Net-(U1-BOOT0)") (class "Default")
      (node (ref "R14") (pin "2") (pinfunction "2_2") (pintype "passive"))
      (node (ref "U1") (pin "60") (pinfunction "BOOT0_60") (pintype "bidirectional"))
    )
    (net (code "51") (name "Net-(U1-PA0)") (class "Default")
      (node (ref "R26") (pin "1") (pinfunction "1_1") (pintype "passive"))
      (node (ref "R27") (pin "2") (pinfunction "2_2") (pintype "passive"))
      (node (ref "U1") (pin "14") (pinfunction "PA0_14") (pintype "bidirectional"))
    )
    (net (code "52") (name "Net-(U1-VCAP1)") (class "Default")
      (node (ref "C9") (pin "2") (pinfunction "2_2") (pintype "passive"))
      (node (ref "U1") (pin "30") (pinfunction "VCAP1_30") (pintype "bidirectional"))
    )
    (net (code "53") (name "Net-(U1-VDDA)") (class "Default")
      (node (ref "C41") (pin "1") (pinfunction "1_1") (pintype "passive"))
      (node (ref "CHOKE") (pin "2") (pinfunction "2_2") (pintype "passive"))
      (node (ref "U1") (pin "13") (pinfunction "VDDA_13") (pintype "bidirectional"))
    )
    (net (code "54") (name "PHASA") (class "Default")
      (node (ref "DRV1") (pin "9") (pinfunction "SHA_9") (pintype "bidirectional"))
      (node (ref "O_A") (pin "P$1") (pinfunction "P$1_P$1") (pintype "bidirectional"))
      (node (ref "Q7") (pin "1") (pinfunction "S_1") (pintype "bidirectional"))
      (node (ref "Q7") (pin "2") (pinfunction "S_2") (pintype "bidirectional"))
      (node (ref "Q7") (pin "3") (pinfunction "S_3") (pintype "bidirectional"))
      (node (ref "Q8") (pin "10") (pinfunction "D_10") (pintype "bidirectional"))
      (node (ref "Q8") (pin "11") (pinfunction "D_11") (pintype "bidirectional"))
      (node (ref "Q8") (pin "5") (pinfunction "D_5") (pintype "bidirectional"))
      (node (ref "Q8") (pin "6") (pinfunction "D_6") (pintype "bidirectional"))
      (node (ref "Q8") (pin "7") (pinfunction "D_7") (pintype "bidirectional"))
      (node (ref "Q8") (pin "8") (pinfunction "D_8") (pintype "bidirectional"))
      (node (ref "Q8") (pin "9") (pinfunction "D_9") (pintype "bidirectional"))
    )
    (net (code "55") (name "PHASB") (class "Default")
      (node (ref "DRV1") (pin "16") (pinfunction "SHB_16") (pintype "bidirectional"))
      (node (ref "O_B") (pin "P$1") (pinfunction "P$1_P$1") (pintype "bidirectional"))
      (node (ref "Q10") (pin "10") (pinfunction "D_10") (pintype "bidirectional"))
      (node (ref "Q10") (pin "11") (pinfunction "D_11") (pintype "bidirectional"))
      (node (ref "Q10") (pin "5") (pinfunction "D_5") (pintype "bidirectional"))
      (node (ref "Q10") (pin "6") (pinfunction "D_6") (pintype "bidirectional"))
      (node (ref "Q10") (pin "7") (pinfunction "D_7") (pintype "bidirectional"))
      (node (ref "Q10") (pin "8") (pinfunction "D_8") (pintype "bidirectional"))
      (node (ref "Q10") (pin "9") (pinfunction "D_9") (pintype "bidirectional"))
      (node (ref "Q9") (pin "1") (pinfunction "S_1") (pintype "bidirectional"))
      (node (ref "Q9") (pin "2") (pinfunction "S_2") (pintype "bidirectional"))
      (node (ref "Q9") (pin "3") (pinfunction "S_3") (pintype "bidirectional"))
    )
    (net (code "56") (name "PHASC") (class "Default")
      (node (ref "DRV1") (pin "19") (pinfunction "SHC_19") (pintype "bidirectional"))
      (node (ref "O_C") (pin "P$1") (pinfunction "P$1_P$1") (pintype "bidirectional"))
      (node (ref "Q11") (pin "1") (pinfunction "S_1") (pintype "bidirectional"))
      (node (ref "Q11") (pin "2") (pinfunction "S_2") (pintype "bidirectional"))
      (node (ref "Q11") (pin "3") (pinfunction "S_3") (pintype "bidirectional"))
      (node (ref "Q12") (pin "10") (pinfunction "D_10") (pintype "bidirectional"))
      (node (ref "Q12") (pin "11") (pinfunction "D_11") (pintype "bidirectional"))
      (node (ref "Q12") (pin "5") (pinfunction "D_5") (pintype "bidirectional"))
      (node (ref "Q12") (pin "6") (pinfunction "D_6") (pintype "bidirectional"))
      (node (ref "Q12") (pin "7") (pinfunction "D_7") (pintype "bidirectional"))
      (node (ref "Q12") (pin "8") (pinfunction "D_8") (pintype "bidirectional"))
      (node (ref "Q12") (pin "9") (pinfunction "D_9") (pintype "bidirectional"))
    )
    (net (code "57") (name "PWMA") (class "Default")
      (node (ref "DRV1") (pin "41") (pinfunction "INHC_41") (pintype "bidirectional"))
      (node (ref "U1") (pin "43") (pinfunction "PA10/UART1_RX_43") (pintype "bidirectional"))
    )
    (net (code "58") (name "PWMB") (class "Default")
      (node (ref "DRV1") (pin "39") (pinfunction "INHB_39") (pintype "bidirectional"))
      (node (ref "U1") (pin "42") (pinfunction "PA9/UART1_TX_42") (pintype "bidirectional"))
    )
    (net (code "59") (name "PWMC") (class "Default")
      (node (ref "DRV1") (pin "37") (pinfunction "INHA_37") (pintype "bidirectional"))
      (node (ref "U1") (pin "41") (pinfunction "PA8_41") (pintype "bidirectional"))
    )
    (net (code "60") (name "SPA") (class "Default")
      (node (ref "DRV1") (pin "11") (pinfunction "SPA_11") (pintype "bidirectional"))
      (node (ref "Q8") (pin "1") (pinfunction "S_1") (pintype "bidirectional"))
      (node (ref "Q8") (pin "2") (pinfunction "S_2") (pintype "bidirectional"))
      (node (ref "Q8") (pin "3") (pinfunction "S_3") (pintype "bidirectional"))
      (node (ref "R8") (pin "2") (pinfunction "2_2") (pintype "passive"))
    )
    (net (code "61") (name "SPB") (class "Default")
      (node (ref "DRV1") (pin "14") (pinfunction "SPB_14") (pintype "bidirectional"))
      (node (ref "Q10") (pin "1") (pinfunction "S_1") (pintype "bidirectional"))
      (node (ref "Q10") (pin "2") (pinfunction "S_2") (pintype "bidirectional"))
      (node (ref "Q10") (pin "3") (pinfunction "S_3") (pintype "bidirectional"))
      (node (ref "R9") (pin "2") (pinfunction "2_2") (pintype "passive"))
    )
    (net (code "62") (name "SPI-MISO") (class "Default")
      (node (ref "DRV1") (pin "29") (pinfunction "MODE_29") (pintype "bidirectional"))
      (node (ref "R3") (pin "1") (pinfunction "1_1") (pintype "passive"))
      (node (ref "U1") (pin "22") (pinfunction "PA6/SPI1_MISO_22") (pintype "bidirectional"))
    )
    (net (code "63") (name "SPI-MOSI") (class "Default")
      (node (ref "DRV1") (pin "30") (pinfunction "IDRIVE_30") (pintype "bidirectional"))
      (node (ref "U1") (pin "23") (pinfunction "PA7/SPI1_MOSI_23") (pintype "bidirectional"))
    )
    (net (code "64") (name "SPI-NSS-DRV") (class "Default")
      (node (ref "DRV1") (pin "32") (pinfunction "GAIN_32") (pintype "bidirectional"))
      (node (ref "U1") (pin "20") (pinfunction "PA4/SPI1_NSS_20") (pintype "bidirectional"))
    )
    (net (code "65") (name "SPI-SCK") (class "Default")
      (node (ref "DRV1") (pin "31") (pinfunction "VDS_31") (pintype "bidirectional"))
      (node (ref "U1") (pin "21") (pinfunction "PA5/SPI1_SCK_21") (pintype "bidirectional"))
    )
    (net (code "66") (name "unconnected-(DRV1-NC-Pad46)") (class "Default")
      (node (ref "DRV1") (pin "46") (pinfunction "NC_46") (pintype "bidirectional"))
    )
    (net (code "67") (name "unconnected-(DRV1-NSHDN-Pad48)") (class "Default")
      (node (ref "DRV1") (pin "48") (pinfunction "NSHDN_48") (pintype "bidirectional"))
    )
    (net (code "68") (name "unconnected-(U1-PA1-Pad15)") (class "Default")
      (node (ref "U1") (pin "15") (pinfunction "PA1_15") (pintype "bidirectional"))
    )
    (net (code "69") (name "unconnected-(U1-PA12-Pad45)") (class "Default")
      (node (ref "U1") (pin "45") (pinfunction "PA12_45") (pintype "bidirectional"))
    )
    (net (code "70") (name "unconnected-(U1-PB0-Pad26)") (class "Default")
      (node (ref "U1") (pin "26") (pinfunction "PB0_26") (pintype "bidirectional"))
    )
    (net (code "71") (name "unconnected-(U1-PB1-Pad27)") (class "Default")
      (node (ref "U1") (pin "27") (pinfunction "PB1_27") (pintype "bidirectional"))
    )
    (net (code "72") (name "unconnected-(U1-PB2-BOOT1-Pad28)") (class "Default")
      (node (ref "U1") (pin "28") (pinfunction "PB2-BOOT1_28") (pintype "bidirectional"))
    )
    (net (code "73") (name "unconnected-(U1-PB3{slash}JTDO-Pad55)") (class "Default")
      (node (ref "U1") (pin "55") (pinfunction "PB3/JTDO_55") (pintype "bidirectional"))
    )
    (net (code "74") (name "unconnected-(U1-PB4{slash}JTRST-Pad56)") (class "Default")
      (node (ref "U1") (pin "56") (pinfunction "PB4/JTRST_56") (pintype "bidirectional"))
    )
    (net (code "75") (name "unconnected-(U1-PB5-Pad57)") (class "Default")
      (node (ref "U1") (pin "57") (pinfunction "PB5_57") (pintype "bidirectional"))
    )
    (net (code "76") (name "unconnected-(U1-PB10-Pad29)") (class "Default")
      (node (ref "U1") (pin "29") (pinfunction "PB10_29") (pintype "bidirectional"))
    )
    (net (code "77") (name "unconnected-(U1-PB12{slash}I2S2_WS-Pad33)") (class "Default")
      (node (ref "U1") (pin "33") (pinfunction "PB12/I2S2_WS_33") (pintype "bidirectional"))
    )
    (net (code "78") (name "unconnected-(U1-PB13{slash}I2S2_CK-Pad34)") (class "Default")
      (node (ref "U1") (pin "34") (pinfunction "PB13/I2S2_CK_34") (pintype "bidirectional"))
    )
    (net (code "79") (name "unconnected-(U1-PC2-Pad10)") (class "Default")
      (node (ref "U1") (pin "10") (pinfunction "PC2_10") (pintype "bidirectional"))
    )
    (net (code "80") (name "unconnected-(U1-PC3-Pad11)") (class "Default")
      (node (ref "U1") (pin "11") (pinfunction "PC3_11") (pintype "bidirectional"))
    )
    (net (code "81") (name "unconnected-(U1-PC4-Pad24)") (class "Default")
      (node (ref "U1") (pin "24") (pinfunction "PC4_24") (pintype "bidirectional"))
    )
    (net (code "82") (name "unconnected-(U1-PC6{slash}I2S2_MCK-Pad37)") (class "Default")
      (node (ref "U1") (pin "37") (pinfunction "PC6/I2S2_MCK_37") (pintype "bidirectional"))
    )
    (net (code "83") (name "unconnected-(U1-PC7-Pad38)") (class "Default")
      (node (ref "U1") (pin "38") (pinfunction "PC7_38") (pintype "bidirectional"))
    )
    (net (code "84") (name "unconnected-(U1-PC8{slash}SDIO_D0-Pad39)") (class "Default")
      (node (ref "U1") (pin "39") (pinfunction "PC8/SDIO_D0_39") (pintype "bidirectional"))
    )
    (net (code "85") (name "unconnected-(U1-PC9{slash}SDIO_D1-Pad40)") (class "Default")
      (node (ref "U1") (pin "40") (pinfunction "PC9/SDIO_D1_40") (pintype "bidirectional"))
    )
    (net (code "86") (name "unconnected-(U1-PC13-Pad2)") (class "Default")
      (node (ref "U1") (pin "2") (pinfunction "PC13_2") (pintype "bidirectional"))
    )
    (net (code "87") (name "unconnected-(U1-PC14-Pad3)") (class "Default")
      (node (ref "U1") (pin "3") (pinfunction "PC14_3") (pintype "bidirectional"))
    )
    (net (code "88") (name "unconnected-(U1-PC15-Pad4)") (class "Default")
      (node (ref "U1") (pin "4") (pinfunction "PC15_4") (pintype "bidirectional"))
    )
    (net (code "89") (name "unconnected-(U1-PD2{slash}SDIO_CMD-Pad54)") (class "Default")
      (node (ref "U1") (pin "54") (pinfunction "PD2/SDIO_CMD_54") (pintype "bidirectional"))
    )
    (net (code "90") (name "unconnected-(U3-ADJ-Pad5)") (class "Default")
      (node (ref "U3") (pin "5") (pinfunction "ADJ_5") (pintype "input"))
    )
    (net (code "91") (name "unconnected-(U3-PG-Pad3)") (class "Default")
      (node (ref "U3") (pin "3") (pinfunction "PG_3") (pintype "bidirectional"))
    )
  )
)
